# EEM_connector.net
KiCad netlist of a schematic drawn in Altium Designer
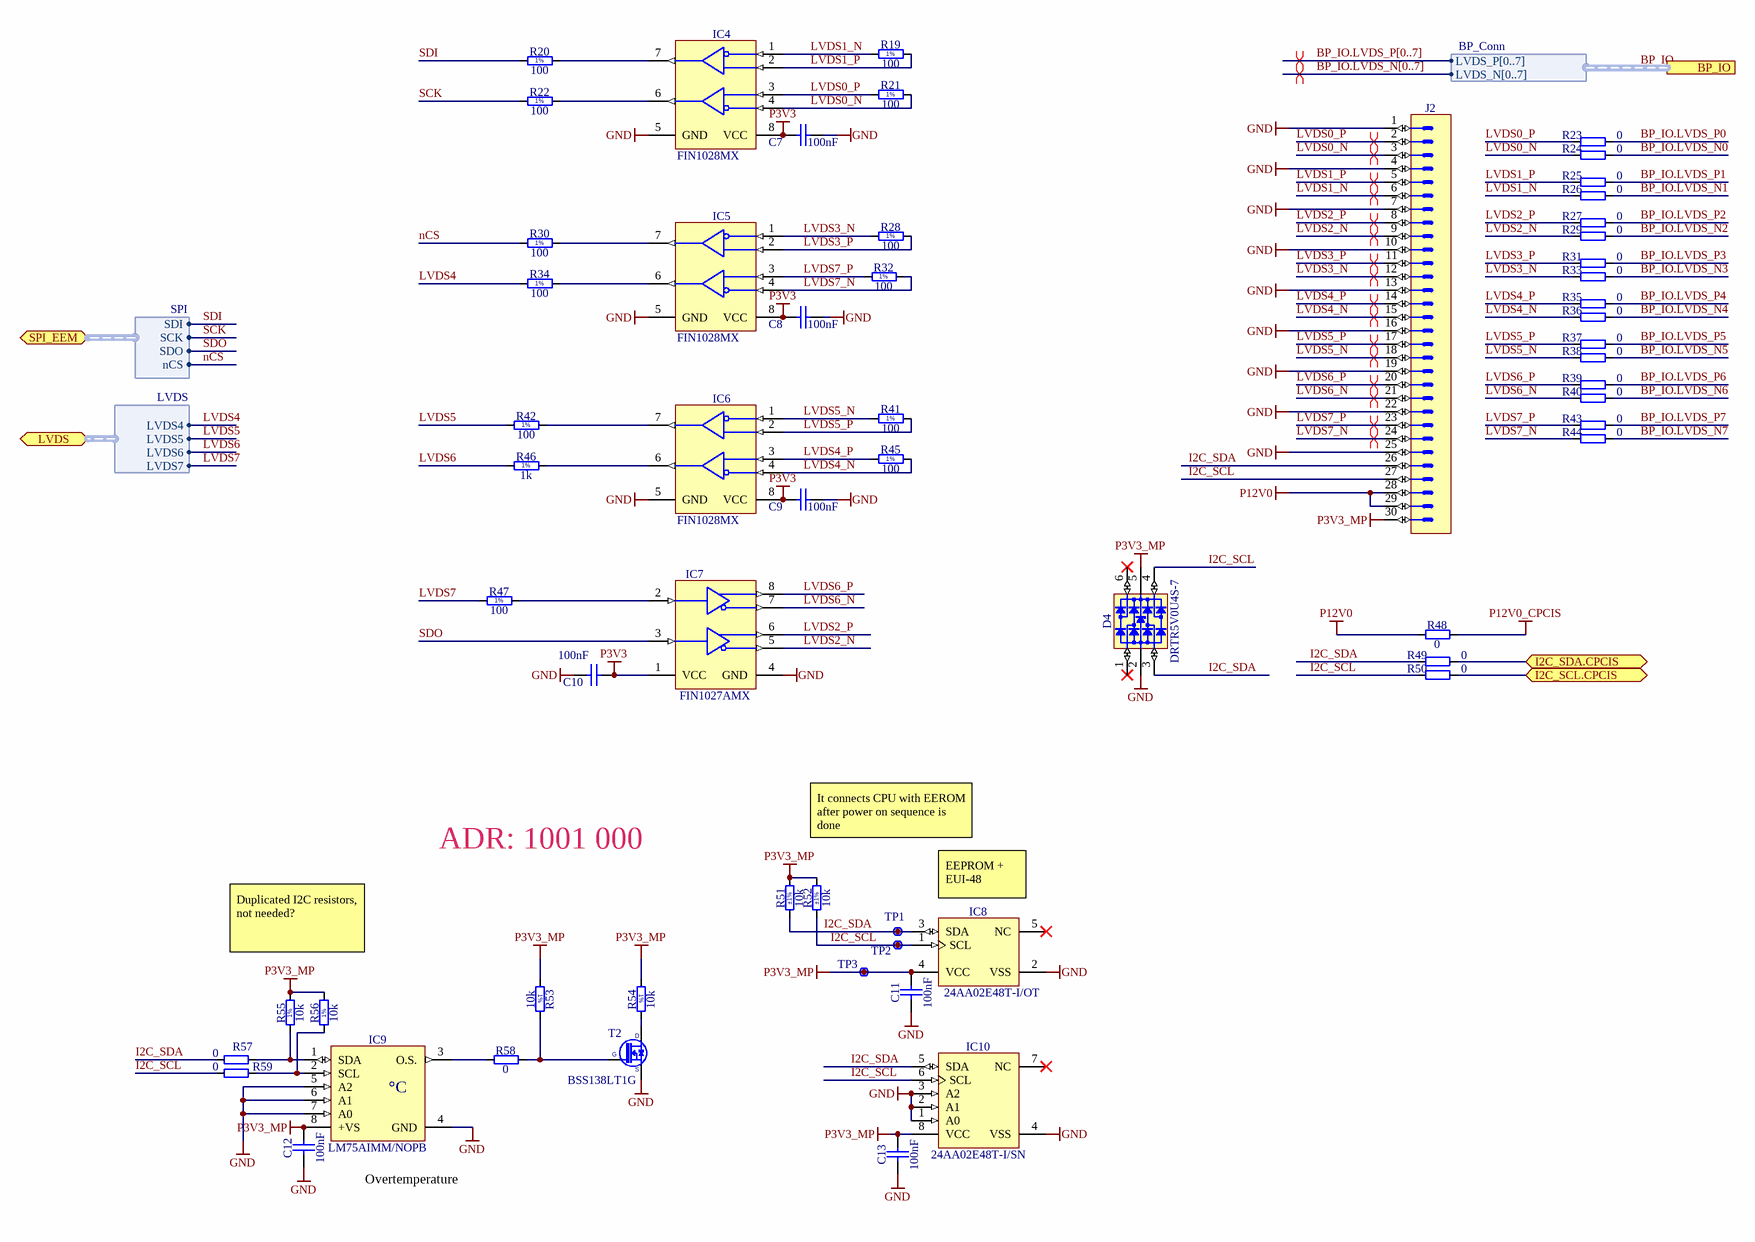
[diagram p0: EEM_connector.SchDoc]

(export (version "E")
  (design (tool "Eeschema 10.0.6"))
  (components
    (comp (ref "C7")
      (value "100nF")
      (footprint "CAPC1005X55N")
      (description "Non-polarised capacitor")
      (fields
        (field (name "PART NUMBER") "CC0402_100NF_16V_10%_X5R")
        (field (name "VOLTAGE") "16V")
        (field (name "AUTHOR") "CERN DEM JLC")
      )
      (libsource (lib "Capacitors") (part "Capacitor - non polarized"))
    )
    (comp (ref "C8")
      (value "100nF")
      (footprint "CAPC1005X55N")
      (description "Non-polarised capacitor")
      (fields
        (field (name "PART NUMBER") "CC0402_100NF_16V_10%_X5R")
        (field (name "VOLTAGE") "16V")
        (field (name "AUTHOR") "CERN DEM JLC")
      )
      (libsource (lib "Capacitors") (part "Capacitor - non polarized"))
    )
    (comp (ref "C9")
      (value "100nF")
      (footprint "CAPC1005X55N")
      (description "Non-polarised capacitor")
      (fields
        (field (name "PART NUMBER") "CC0402_100NF_16V_10%_X5R")
        (field (name "VOLTAGE") "16V")
        (field (name "AUTHOR") "CERN DEM JLC")
      )
      (libsource (lib "Capacitors") (part "Capacitor - non polarized"))
    )
    (comp (ref "C10")
      (value "100nF")
      (footprint "CAPC1005X55N")
      (description "Non-polarised capacitor")
      (fields
        (field (name "PART NUMBER") "CC0402_100NF_16V_10%_X5R")
        (field (name "VOLTAGE") "16V")
        (field (name "AUTHOR") "CERN DEM JLC")
      )
      (libsource (lib "Capacitors") (part "Capacitor - non polarized"))
    )
    (comp (ref "C11")
      (value "100nF")
      (footprint "CAPC1005X55N")
      (description "Non-polarised capacitor")
      (fields
        (field (name "PART NUMBER") "CC0402_100NF_16V_10%_X5R")
        (field (name "VOLTAGE") "16V")
        (field (name "AUTHOR") "CERN DEM JLC")
      )
      (libsource (lib "Capacitors") (part "Capacitor - non polarized"))
    )
    (comp (ref "C12")
      (value "100nF")
      (footprint "CAPC1005X55N")
      (description "Non-polarised capacitor")
      (fields
        (field (name "PART NUMBER") "CC0402_100NF_16V_10%_X5R")
        (field (name "VOLTAGE") "16V")
        (field (name "AUTHOR") "CERN DEM JLC")
      )
      (libsource (lib "Capacitors") (part "Capacitor - non polarized"))
    )
    (comp (ref "C13")
      (value "100nF")
      (footprint "CAPC1005X55N")
      (description "Non-polarised capacitor")
      (fields
        (field (name "PART NUMBER") "CC0402_100NF_16V_10%_X5R")
        (field (name "VOLTAGE") "16V")
        (field (name "AUTHOR") "CERN DEM JLC")
      )
      (libsource (lib "Capacitors") (part "Capacitor - non polarized"))
    )
    (comp (ref "D4")
      (value "DRTR5V0U4S-7")
      (footprint "SOT65P210X110-6N")
      (description "Integrated Quad Ultra-Low Capacitance ESD Protection")
      (fields (field (name "MANUFACTURER") "DIODES") (field (name "AUTHOR") "GK"))
      (libsource (lib "Diodes") (part "D_TVS_DRTR5V0U4S-7"))
    )
    (comp (ref "IC4")
      (value "FIN1028MX")
      (footprint "SOIC127P600X175-8N")
      (description "3.3V LVDS 2-Bit High-Speed Differential Reciever")
      (fields (field (name "MANUFACTURER") "ON Semiconductor") (field (name "AUTHOR") "GK"))
      (libsource (lib "LIBRARY_SCH") (part "IFC_FIN1028"))
    )
    (comp (ref "IC5")
      (value "FIN1028MX")
      (footprint "SOIC127P600X175-8N")
      (description "3.3V LVDS 2-Bit High-Speed Differential Reciever")
      (fields (field (name "MANUFACTURER") "ON Semiconductor") (field (name "AUTHOR") "GK"))
      (libsource (lib "LIBRARY_SCH") (part "IFC_FIN1028"))
    )
    (comp (ref "IC6")
      (value "FIN1028MX")
      (footprint "SOIC127P600X175-8N")
      (description "3.3V LVDS 2-Bit High-Speed Differential Reciever")
      (fields (field (name "MANUFACTURER") "ON Semiconductor") (field (name "AUTHOR") "GK"))
      (libsource (lib "LIBRARY_SCH") (part "IFC_FIN1028"))
    )
    (comp (ref "IC7")
      (value "FIN1027AMX")
      (footprint "SOIC127P600X175-8N")
      (description "3.3V LVDS, 2-Bit, High-Speed, Differential Driver")
      (fields (field (name "MANUFACTURER") "ON Semiconductor") (field (name "AUTHOR") "GK"))
      (libsource (lib "LIBRARY_SCH") (part "IFC_FIN1027A"))
    )
    (comp (ref "IC8")
      (value "24AA02E48T-I/OT")
      (footprint "SOT95P280X145-5N")
      (description "1.7V-5.5V, 2K I2C Serial EEPROM With EUI-48 Node Identity")
      (fields (field (name "MANUFACTURER") "MICROCHIP TECHNOLOGY") (field (name "AUTHOR") "CERN DEM MR"))
      (libsource (lib "ICs And Semiconductors") (part "24AA02E48T-I/OT"))
    )
    (comp (ref "IC9")
      (value "LM75AIMM/NOPB")
      (footprint "SOP65P490X109-8N")
      (description "Digital Temperature Sensor and Thermal Watchdog with Two-Wire Interface")
      (fields (field (name "MANUFACTURER") "TEXAS INSTRUMENTS") (field (name "AUTHOR") "CERN DEM JLC"))
      (libsource (lib "ICs And Semiconductors") (part "LM75"))
    )
    (comp (ref "IC10")
      (value "24AA02E48T-I/SN")
      (footprint "SOIC127P600X175-8N")
      (description "1.7V-5.5V, 2K I2C™ Serial EEPROMs with EUI-48™ Node Identity")
      (fields (field (name "MANUFACTURER") "MICROCHIP TECHNOLOGY") (field (name "AUTHOR") "CERN DEM MR"))
      (libsource (lib "ICs And Semiconductors") (part "24AA025E48-I/SN"))
    )
    (comp (ref "J2")
      (value "IDC")
      (footprint "3M_N2530-6002RB")
      (description "Connector 30 Male")
      (fields
        (field (name "PART NUMBER") "3M_N2530-6002RB")
        (field (name "MANUFACTURER") "3M")
        (field (name "AUTHOR") "CERN DEM JLC")
      )
      (libsource (lib "Connectors") (part "Connector 30 Male"))
    )
    (comp (ref "R19")
      (value "100")
      (footprint "RESC1005X40N")
      (description "Resistor - 1%")
      (fields
        (field (name "PART NUMBER") "R0402_100R_1%_0.0625W_100PPM")
        (field (name "POWER") "0.0625W")
        (field (name "AUTHOR") "CERN DEM JLC")
      )
      (libsource (lib "Resistors") (part "Resistor - 1%"))
    )
    (comp (ref "R20")
      (value "100")
      (footprint "RESC1005X40N")
      (description "Resistor - 1%")
      (fields
        (field (name "PART NUMBER") "R0402_100R_1%_0.0625W_100PPM")
        (field (name "POWER") "0.0625W")
        (field (name "AUTHOR") "CERN DEM JLC")
      )
      (libsource (lib "Resistors") (part "Resistor - 1%"))
    )
    (comp (ref "R21")
      (value "100")
      (footprint "RESC1005X40N")
      (description "Resistor - 1%")
      (fields
        (field (name "PART NUMBER") "R0402_100R_1%_0.0625W_100PPM")
        (field (name "POWER") "0.0625W")
        (field (name "AUTHOR") "CERN DEM JLC")
      )
      (libsource (lib "Resistors") (part "Resistor - 1%"))
    )
    (comp (ref "R22")
      (value "100")
      (footprint "RESC1005X40N")
      (description "Resistor - 1%")
      (fields
        (field (name "PART NUMBER") "R0402_100R_1%_0.0625W_100PPM")
        (field (name "POWER") "0.0625W")
        (field (name "AUTHOR") "CERN DEM JLC")
      )
      (libsource (lib "Resistors") (part "Resistor - 1%"))
    )
    (comp (ref "R23")
      (value "0")
      (footprint "RESC1005X40N")
      (description "Resistor")
      (fields
        (field (name "PART NUMBER") "R0402_0R_JUMPER")
        (field (name "MANUFACTURER") "GENERIC")
        (field (name "AUTHOR") "CERN DEM JLC")
      )
      (libsource (lib "Resistors") (part "Resistor"))
    )
    (comp (ref "R24")
      (value "0")
      (footprint "RESC1005X40N")
      (description "Resistor")
      (fields
        (field (name "PART NUMBER") "R0402_0R_JUMPER")
        (field (name "MANUFACTURER") "GENERIC")
        (field (name "AUTHOR") "CERN DEM JLC")
      )
      (libsource (lib "Resistors") (part "Resistor"))
    )
    (comp (ref "R25")
      (value "0")
      (footprint "RESC1005X40N")
      (description "Resistor")
      (fields
        (field (name "PART NUMBER") "R0402_0R_JUMPER")
        (field (name "MANUFACTURER") "GENERIC")
        (field (name "AUTHOR") "CERN DEM JLC")
      )
      (libsource (lib "Resistors") (part "Resistor"))
    )
    (comp (ref "R26")
      (value "0")
      (footprint "RESC1005X40N")
      (description "Resistor")
      (fields
        (field (name "PART NUMBER") "R0402_0R_JUMPER")
        (field (name "MANUFACTURER") "GENERIC")
        (field (name "AUTHOR") "CERN DEM JLC")
      )
      (libsource (lib "Resistors") (part "Resistor"))
    )
    (comp (ref "R27")
      (value "0")
      (footprint "RESC1005X40N")
      (description "Resistor")
      (fields
        (field (name "PART NUMBER") "R0402_0R_JUMPER")
        (field (name "MANUFACTURER") "GENERIC")
        (field (name "AUTHOR") "CERN DEM JLC")
      )
      (libsource (lib "Resistors") (part "Resistor"))
    )
    (comp (ref "R28")
      (value "100")
      (footprint "RESC1005X40N")
      (description "Resistor - 1%")
      (fields
        (field (name "PART NUMBER") "R0402_100R_1%_0.0625W_100PPM")
        (field (name "POWER") "0.0625W")
        (field (name "AUTHOR") "CERN DEM JLC")
      )
      (libsource (lib "Resistors") (part "Resistor - 1%"))
    )
    (comp (ref "R29")
      (value "0")
      (footprint "RESC1005X40N")
      (description "Resistor")
      (fields
        (field (name "PART NUMBER") "R0402_0R_JUMPER")
        (field (name "MANUFACTURER") "GENERIC")
        (field (name "AUTHOR") "CERN DEM JLC")
      )
      (libsource (lib "Resistors") (part "Resistor"))
    )
    (comp (ref "R30")
      (value "100")
      (footprint "RESC1005X40N")
      (description "Resistor - 1%")
      (fields
        (field (name "PART NUMBER") "R0402_100R_1%_0.0625W_100PPM")
        (field (name "POWER") "0.0625W")
        (field (name "AUTHOR") "CERN DEM JLC")
      )
      (libsource (lib "Resistors") (part "Resistor - 1%"))
    )
    (comp (ref "R31")
      (value "0")
      (footprint "RESC1005X40N")
      (description "Resistor")
      (fields
        (field (name "PART NUMBER") "R0402_0R_JUMPER")
        (field (name "MANUFACTURER") "GENERIC")
        (field (name "AUTHOR") "CERN DEM JLC")
      )
      (libsource (lib "Resistors") (part "Resistor"))
    )
    (comp (ref "R32")
      (value "100")
      (footprint "RESC1005X40N")
      (description "Resistor - 1%")
      (fields
        (field (name "PART NUMBER") "R0402_100R_1%_0.0625W_100PPM")
        (field (name "POWER") "0.0625W")
        (field (name "AUTHOR") "CERN DEM JLC")
      )
      (libsource (lib "Resistors") (part "Resistor - 1%"))
    )
    (comp (ref "R33")
      (value "0")
      (footprint "RESC1005X40N")
      (description "Resistor")
      (fields
        (field (name "PART NUMBER") "R0402_0R_JUMPER")
        (field (name "MANUFACTURER") "GENERIC")
        (field (name "AUTHOR") "CERN DEM JLC")
      )
      (libsource (lib "Resistors") (part "Resistor"))
    )
    (comp (ref "R34")
      (value "100")
      (footprint "RESC1005X40N")
      (description "Resistor - 1%")
      (fields
        (field (name "PART NUMBER") "R0402_100R_1%_0.0625W_100PPM")
        (field (name "POWER") "0.0625W")
        (field (name "AUTHOR") "CERN DEM JLC")
      )
      (libsource (lib "Resistors") (part "Resistor - 1%"))
    )
    (comp (ref "R35")
      (value "0")
      (footprint "RESC1005X40N")
      (description "Resistor")
      (fields
        (field (name "PART NUMBER") "R0402_0R_JUMPER")
        (field (name "MANUFACTURER") "GENERIC")
        (field (name "AUTHOR") "CERN DEM JLC")
      )
      (libsource (lib "Resistors") (part "Resistor"))
    )
    (comp (ref "R36")
      (value "0")
      (footprint "RESC1005X40N")
      (description "Resistor")
      (fields
        (field (name "PART NUMBER") "R0402_0R_JUMPER")
        (field (name "MANUFACTURER") "GENERIC")
        (field (name "AUTHOR") "CERN DEM JLC")
      )
      (libsource (lib "Resistors") (part "Resistor"))
    )
    (comp (ref "R37")
      (value "0")
      (footprint "RESC1005X40N")
      (description "Resistor")
      (fields
        (field (name "PART NUMBER") "R0402_0R_JUMPER")
        (field (name "MANUFACTURER") "GENERIC")
        (field (name "AUTHOR") "CERN DEM JLC")
      )
      (libsource (lib "Resistors") (part "Resistor"))
    )
    (comp (ref "R38")
      (value "0")
      (footprint "RESC1005X40N")
      (description "Resistor")
      (fields
        (field (name "PART NUMBER") "R0402_0R_JUMPER")
        (field (name "MANUFACTURER") "GENERIC")
        (field (name "AUTHOR") "CERN DEM JLC")
      )
      (libsource (lib "Resistors") (part "Resistor"))
    )
    (comp (ref "R39")
      (value "0")
      (footprint "RESC1005X40N")
      (description "Resistor")
      (fields
        (field (name "PART NUMBER") "R0402_0R_JUMPER")
        (field (name "MANUFACTURER") "GENERIC")
        (field (name "AUTHOR") "CERN DEM JLC")
      )
      (libsource (lib "Resistors") (part "Resistor"))
    )
    (comp (ref "R40")
      (value "0")
      (footprint "RESC1005X40N")
      (description "Resistor")
      (fields
        (field (name "PART NUMBER") "R0402_0R_JUMPER")
        (field (name "MANUFACTURER") "GENERIC")
        (field (name "AUTHOR") "CERN DEM JLC")
      )
      (libsource (lib "Resistors") (part "Resistor"))
    )
    (comp (ref "R41")
      (value "100")
      (footprint "RESC1005X40N")
      (description "Resistor - 1%")
      (fields
        (field (name "PART NUMBER") "R0402_100R_1%_0.0625W_100PPM")
        (field (name "POWER") "0.0625W")
        (field (name "AUTHOR") "CERN DEM JLC")
      )
      (libsource (lib "Resistors") (part "Resistor - 1%"))
    )
    (comp (ref "R42")
      (value "100")
      (footprint "RESC1005X40N")
      (description "Resistor - 1%")
      (fields
        (field (name "PART NUMBER") "R0402_100R_1%_0.0625W_100PPM")
        (field (name "POWER") "0.0625W")
        (field (name "AUTHOR") "CERN DEM JLC")
      )
      (libsource (lib "Resistors") (part "Resistor - 1%"))
    )
    (comp (ref "R43")
      (value "0")
      (footprint "RESC1005X40N")
      (description "Resistor")
      (fields
        (field (name "PART NUMBER") "R0402_0R_JUMPER")
        (field (name "MANUFACTURER") "GENERIC")
        (field (name "AUTHOR") "CERN DEM JLC")
      )
      (libsource (lib "Resistors") (part "Resistor"))
    )
    (comp (ref "R44")
      (value "0")
      (footprint "RESC1005X40N")
      (description "Resistor")
      (fields
        (field (name "PART NUMBER") "R0402_0R_JUMPER")
        (field (name "MANUFACTURER") "GENERIC")
        (field (name "AUTHOR") "CERN DEM JLC")
      )
      (libsource (lib "Resistors") (part "Resistor"))
    )
    (comp (ref "R45")
      (value "100")
      (footprint "RESC1005X40N")
      (description "Resistor - 1%")
      (fields
        (field (name "PART NUMBER") "R0402_100R_1%_0.0625W_100PPM")
        (field (name "POWER") "0.0625W")
        (field (name "AUTHOR") "CERN DEM JLC")
      )
      (libsource (lib "Resistors") (part "Resistor - 1%"))
    )
    (comp (ref "R46")
      (value "1k")
      (footprint "RESC1005X40N")
      (description "Resistor - 1%")
      (fields
        (field (name "PART NUMBER") "R0402_1K_1%_0.0625W_100PPM")
        (field (name "POWER") "0.0625W")
        (field (name "AUTHOR") "CERN DEM JLC")
      )
      (libsource (lib "Resistors") (part "Resistor - 1%"))
    )
    (comp (ref "R47")
      (value "100")
      (footprint "RESC1005X40N")
      (description "Resistor - 1%")
      (fields
        (field (name "PART NUMBER") "R0402_100R_1%_0.0625W_100PPM")
        (field (name "POWER") "0.0625W")
        (field (name "AUTHOR") "CERN DEM JLC")
      )
      (libsource (lib "Resistors") (part "Resistor - 1%"))
    )
    (comp (ref "R48")
      (value "0")
      (footprint "RESC2012X60N")
      (description "Resistor")
      (fields
        (field (name "PART NUMBER") "R0805_0R_JUMPER")
        (field (name "MANUFACTURER") "GENERIC")
        (field (name "AUTHOR") "CERN DEM JLC")
      )
      (libsource (lib "Resistors") (part "Resistor"))
    )
    (comp (ref "R49")
      (value "0")
      (footprint "RESC1005X40N")
      (description "Resistor")
      (fields
        (field (name "PART NUMBER") "R0402_0R_JUMPER")
        (field (name "MANUFACTURER") "GENERIC")
        (field (name "AUTHOR") "CERN DEM JLC")
      )
      (libsource (lib "Resistors") (part "Resistor"))
    )
    (comp (ref "R50")
      (value "0")
      (footprint "RESC1005X40N")
      (description "Resistor")
      (fields
        (field (name "PART NUMBER") "R0402_0R_JUMPER")
        (field (name "MANUFACTURER") "GENERIC")
        (field (name "AUTHOR") "CERN DEM JLC")
      )
      (libsource (lib "Resistors") (part "Resistor"))
    )
    (comp (ref "R51")
      (value "10k")
      (footprint "RESC1005X40N")
      (description "Resistor - 1%")
      (fields
        (field (name "TOLERANCE") "±1%")
        (field (name "PART NUMBER") "R0402_10K_1%_0.0625W_100PPM")
        (field (name "POWER") "0.0625W")
        (field (name "AUTHOR") "CERN DEM JLC")
      )
      (libsource (lib "Resistors") (part "Resistor - 1%"))
    )
    (comp (ref "R52")
      (value "10k")
      (footprint "RESC1005X40N")
      (description "Resistor - 1%")
      (fields
        (field (name "TOLERANCE") "±1%")
        (field (name "PART NUMBER") "R0402_10K_1%_0.0625W_100PPM")
        (field (name "POWER") "0.0625W")
        (field (name "AUTHOR") "CERN DEM JLC")
      )
      (libsource (lib "Resistors") (part "Resistor - 1%"))
    )
    (comp (ref "R53")
      (value "10k")
      (footprint "RESC1005X40N")
      (description "Resistor - 1%")
      (fields
        (field (name "PART NUMBER") "R0402_10K_1%_0.0625W_100PPM")
        (field (name "POWER") "0.0625W")
        (field (name "AUTHOR") "CERN DEM JLC")
      )
      (libsource (lib "Resistors") (part "Resistor - 1%"))
    )
    (comp (ref "R54")
      (value "10k")
      (footprint "RESC1005X40N")
      (description "Resistor - 1%")
      (fields
        (field (name "PART NUMBER") "R0402_10K_1%_0.0625W_100PPM")
        (field (name "POWER") "0.0625W")
        (field (name "AUTHOR") "CERN DEM JLC")
      )
      (libsource (lib "Resistors") (part "Resistor - 1%"))
    )
    (comp (ref "R55")
      (value "10k")
      (footprint "RESC1005X40N")
      (description "Resistor - 1%")
      (fields
        (field (name "PART NUMBER") "R0402_10K_1%_0.0625W_100PPM")
        (field (name "POWER") "0.0625W")
        (field (name "AUTHOR") "CERN DEM JLC")
      )
      (libsource (lib "Resistors") (part "Resistor - 1%"))
    )
    (comp (ref "R56")
      (value "10k")
      (footprint "RESC1005X40N")
      (description "Resistor - 1%")
      (fields
        (field (name "PART NUMBER") "R0402_10K_1%_0.0625W_100PPM")
        (field (name "POWER") "0.0625W")
        (field (name "AUTHOR") "CERN DEM JLC")
      )
      (libsource (lib "Resistors") (part "Resistor - 1%"))
    )
    (comp (ref "R57")
      (value "0")
      (footprint "RESC1005X40N")
      (description "Resistor")
      (fields
        (field (name "PART NUMBER") "R0402_0R_JUMPER")
        (field (name "MANUFACTURER") "GENERIC")
        (field (name "AUTHOR") "CERN DEM JLC")
      )
      (libsource (lib "Resistors") (part "Resistor"))
    )
    (comp (ref "R58")
      (value "0")
      (footprint "RESC1005X40N")
      (description "Resistor")
      (fields
        (field (name "PART NUMBER") "R0402_0R_JUMPER")
        (field (name "MANUFACTURER") "GENERIC")
        (field (name "AUTHOR") "CERN DEM JLC")
      )
      (libsource (lib "Resistors") (part "Resistor"))
    )
    (comp (ref "R59")
      (value "0")
      (footprint "RESC1005X40N")
      (description "Resistor")
      (fields
        (field (name "PART NUMBER") "R0402_0R_JUMPER")
        (field (name "MANUFACTURER") "GENERIC")
        (field (name "AUTHOR") "CERN DEM JLC")
      )
      (libsource (lib "Resistors") (part "Resistor"))
    )
    (comp (ref "T2")
      (value "BSS138LT1G")
      (footprint "SOT95P240X110-3N")
      (description "N-CHANNEL MOSFET WITH DIODE")
      (fields (field (name "MANUFACTURER") "ON SEMICONDUCTOR") (field (name "AUTHOR") "CERN DEM JLC"))
      (libsource (lib "ICs And Semiconductors") (part "N-MOSFET-D 1G 2S 3D"))
    )
    (comp (ref "TP1")
      (value "Test Point")
      (footprint "TPS127")
      (fields (field (name "PART NUMBER") "SMD_PAD_1.27X1.27MM") (field (name "AUTHOR") "CERN DEM JLC"))
      (libsource (lib "Eletro-mechanical") (part "Test Point"))
    )
    (comp (ref "TP2")
      (value "Test Point")
      (footprint "TPS127")
      (fields (field (name "PART NUMBER") "SMD_PAD_1.27X1.27MM") (field (name "AUTHOR") "CERN DEM JLC"))
      (libsource (lib "Eletro-mechanical") (part "Test Point"))
    )
    (comp (ref "TP3")
      (value "Test Point")
      (footprint "TPS127")
      (fields (field (name "PART NUMBER") "SMD_PAD_1.27X1.27MM") (field (name "AUTHOR") "CERN DEM JLC"))
      (libsource (lib "Eletro-mechanical") (part "Test Point"))
    )
  )
  (nets
    (net (code "4") (name "/BP_IO.LVDS_N0") (class "Default")
      (node (ref "R24") (pin "2") (pinfunction "2_2") (pintype "passive"))
    )
    (net (code "5") (name "/BP_IO.LVDS_N1") (class "Default")
      (node (ref "R26") (pin "2") (pinfunction "2_2") (pintype "passive"))
    )
    (net (code "6") (name "/BP_IO.LVDS_N2") (class "Default")
      (node (ref "R29") (pin "2") (pinfunction "2_2") (pintype "passive"))
    )
    (net (code "7") (name "/BP_IO.LVDS_N3") (class "Default")
      (node (ref "R33") (pin "2") (pinfunction "2_2") (pintype "passive"))
    )
    (net (code "8") (name "/BP_IO.LVDS_N4") (class "Default")
      (node (ref "R36") (pin "2") (pinfunction "2_2") (pintype "passive"))
    )
    (net (code "9") (name "/BP_IO.LVDS_N5") (class "Default")
      (node (ref "R38") (pin "2") (pinfunction "2_2") (pintype "passive"))
    )
    (net (code "10") (name "/BP_IO.LVDS_N6") (class "Default")
      (node (ref "R40") (pin "2") (pinfunction "2_2") (pintype "passive"))
    )
    (net (code "11") (name "/BP_IO.LVDS_N7") (class "Default")
      (node (ref "R44") (pin "2") (pinfunction "2_2") (pintype "passive"))
    )
    (net (code "13") (name "/BP_IO.LVDS_P0") (class "Default")
      (node (ref "R23") (pin "2") (pinfunction "2_2") (pintype "passive"))
    )
    (net (code "14") (name "/BP_IO.LVDS_P1") (class "Default")
      (node (ref "R25") (pin "2") (pinfunction "2_2") (pintype "passive"))
    )
    (net (code "15") (name "/BP_IO.LVDS_P2") (class "Default")
      (node (ref "R27") (pin "2") (pinfunction "2_2") (pintype "passive"))
    )
    (net (code "16") (name "/BP_IO.LVDS_P3") (class "Default")
      (node (ref "R31") (pin "2") (pinfunction "2_2") (pintype "passive"))
    )
    (net (code "17") (name "/BP_IO.LVDS_P4") (class "Default")
      (node (ref "R35") (pin "2") (pinfunction "2_2") (pintype "passive"))
    )
    (net (code "18") (name "/BP_IO.LVDS_P5") (class "Default")
      (node (ref "R37") (pin "2") (pinfunction "2_2") (pintype "passive"))
    )
    (net (code "19") (name "/BP_IO.LVDS_P6") (class "Default")
      (node (ref "R39") (pin "2") (pinfunction "2_2") (pintype "passive"))
    )
    (net (code "20") (name "/BP_IO.LVDS_P7") (class "Default")
      (node (ref "R43") (pin "2") (pinfunction "2_2") (pintype "passive"))
    )
    (net (code "23") (name "/I2C_SCL") (class "Default")
      (node (ref "D4") (pin "4") (pinfunction "I/O3_4") (pintype "bidirectional"))
      (node (ref "IC10") (pin "6") (pinfunction "SCL_6") (pintype "input"))
      (node (ref "IC8") (pin "1") (pinfunction "SCL_1") (pintype "input"))
      (node (ref "J2") (pin "27") (pinfunction "27_27") (pintype "bidirectional"))
      (node (ref "R50") (pin "1") (pinfunction "1_1") (pintype "passive"))
      (node (ref "R52") (pin "1") (pinfunction "1_1") (pintype "passive"))
      (node (ref "R59") (pin "1") (pinfunction "1_1") (pintype "passive"))
      (node (ref "TP2") (pin "1") (pinfunction "1_1") (pintype "bidirectional"))
    )
    (net (code "24") (name "/I2C_SCL.CPCIS") (class "Default")
      (node (ref "R50") (pin "2") (pinfunction "2_2") (pintype "passive"))
    )
    (net (code "25") (name "/I2C_SDA") (class "Default")
      (node (ref "D4") (pin "3") (pinfunction "I/O2_3") (pintype "bidirectional"))
      (node (ref "IC10") (pin "5") (pinfunction "SDA_5") (pintype "bidirectional"))
      (node (ref "IC8") (pin "3") (pinfunction "SDA_3") (pintype "bidirectional"))
      (node (ref "J2") (pin "26") (pinfunction "26_26") (pintype "bidirectional"))
      (node (ref "R49") (pin "1") (pinfunction "1_1") (pintype "passive"))
      (node (ref "R51") (pin "1") (pinfunction "1_1") (pintype "passive"))
      (node (ref "R57") (pin "1") (pinfunction "1_1") (pintype "passive"))
      (node (ref "TP1") (pin "1") (pinfunction "1_1") (pintype "bidirectional"))
    )
    (net (code "26") (name "/I2C_SDA.CPCIS") (class "Default")
      (node (ref "R49") (pin "2") (pinfunction "2_2") (pintype "passive"))
    )
    (net (code "27") (name "/LVDS0_N") (class "Default")
      (node (ref "IC4") (pin "4") (pinfunction "RIN2-_4") (pintype "input"))
      (node (ref "J2") (pin "3") (pinfunction "3_3") (pintype "bidirectional"))
      (node (ref "R21") (pin "2") (pinfunction "2_2") (pintype "passive"))
      (node (ref "R24") (pin "1") (pinfunction "1_1") (pintype "passive"))
    )
    (net (code "28") (name "/LVDS0_P") (class "Default")
      (node (ref "IC4") (pin "3") (pinfunction "RIN2+_3") (pintype "input"))
      (node (ref "J2") (pin "2") (pinfunction "2_2") (pintype "bidirectional"))
      (node (ref "R21") (pin "1") (pinfunction "1_1") (pintype "passive"))
      (node (ref "R23") (pin "1") (pinfunction "1_1") (pintype "passive"))
    )
    (net (code "29") (name "/LVDS1_N") (class "Default")
      (node (ref "IC4") (pin "1") (pinfunction "RIN1-_1") (pintype "input"))
      (node (ref "J2") (pin "6") (pinfunction "6_6") (pintype "bidirectional"))
      (node (ref "R19") (pin "1") (pinfunction "1_1") (pintype "passive"))
      (node (ref "R26") (pin "1") (pinfunction "1_1") (pintype "passive"))
    )
    (net (code "30") (name "/LVDS1_P") (class "Default")
      (node (ref "IC4") (pin "2") (pinfunction "RIN1+_2") (pintype "input"))
      (node (ref "J2") (pin "5") (pinfunction "5_5") (pintype "bidirectional"))
      (node (ref "R19") (pin "2") (pinfunction "2_2") (pintype "passive"))
      (node (ref "R25") (pin "1") (pinfunction "1_1") (pintype "passive"))
    )
    (net (code "31") (name "/LVDS2_N") (class "Default")
      (node (ref "IC7") (pin "5") (pinfunction "DOUT-_5") (pintype "output"))
      (node (ref "J2") (pin "9") (pinfunction "9_9") (pintype "bidirectional"))
      (node (ref "R29") (pin "1") (pinfunction "1_1") (pintype "passive"))
    )
    (net (code "32") (name "/LVDS2_P") (class "Default")
      (node (ref "IC7") (pin "6") (pinfunction "DOUT+_6") (pintype "output"))
      (node (ref "J2") (pin "8") (pinfunction "8_8") (pintype "bidirectional"))
      (node (ref "R27") (pin "1") (pinfunction "1_1") (pintype "passive"))
    )
    (net (code "33") (name "/LVDS3_N") (class "Default")
      (node (ref "IC5") (pin "1") (pinfunction "RIN1-_1") (pintype "input"))
      (node (ref "J2") (pin "12") (pinfunction "12_12") (pintype "bidirectional"))
      (node (ref "R28") (pin "1") (pinfunction "1_1") (pintype "passive"))
      (node (ref "R33") (pin "1") (pinfunction "1_1") (pintype "passive"))
    )
    (net (code "34") (name "/LVDS3_P") (class "Default")
      (node (ref "IC5") (pin "2") (pinfunction "RIN1+_2") (pintype "input"))
      (node (ref "J2") (pin "11") (pinfunction "11_11") (pintype "bidirectional"))
      (node (ref "R28") (pin "2") (pinfunction "2_2") (pintype "passive"))
      (node (ref "R31") (pin "1") (pinfunction "1_1") (pintype "passive"))
    )
    (net (code "35") (name "/LVDS4") (class "Default")
      (node (ref "R34") (pin "1") (pinfunction "1_1") (pintype "passive"))
    )
    (net (code "36") (name "/LVDS4_N") (class "Default")
      (node (ref "IC6") (pin "4") (pinfunction "RIN2-_4") (pintype "input"))
      (node (ref "J2") (pin "15") (pinfunction "15_15") (pintype "bidirectional"))
      (node (ref "R36") (pin "1") (pinfunction "1_1") (pintype "passive"))
      (node (ref "R45") (pin "2") (pinfunction "2_2") (pintype "passive"))
    )
    (net (code "37") (name "/LVDS4_P") (class "Default")
      (node (ref "IC6") (pin "3") (pinfunction "RIN2+_3") (pintype "input"))
      (node (ref "J2") (pin "14") (pinfunction "14_14") (pintype "bidirectional"))
      (node (ref "R35") (pin "1") (pinfunction "1_1") (pintype "passive"))
      (node (ref "R45") (pin "1") (pinfunction "1_1") (pintype "passive"))
    )
    (net (code "38") (name "/LVDS5") (class "Default")
      (node (ref "R42") (pin "1") (pinfunction "1_1") (pintype "passive"))
    )
    (net (code "39") (name "/LVDS5_N") (class "Default")
      (node (ref "IC6") (pin "1") (pinfunction "RIN1-_1") (pintype "input"))
      (node (ref "J2") (pin "18") (pinfunction "18_18") (pintype "bidirectional"))
      (node (ref "R38") (pin "1") (pinfunction "1_1") (pintype "passive"))
      (node (ref "R41") (pin "1") (pinfunction "1_1") (pintype "passive"))
    )
    (net (code "40") (name "/LVDS5_P") (class "Default")
      (node (ref "IC6") (pin "2") (pinfunction "RIN1+_2") (pintype "input"))
      (node (ref "J2") (pin "17") (pinfunction "17_17") (pintype "bidirectional"))
      (node (ref "R37") (pin "1") (pinfunction "1_1") (pintype "passive"))
      (node (ref "R41") (pin "2") (pinfunction "2_2") (pintype "passive"))
    )
    (net (code "41") (name "/LVDS6") (class "Default")
      (node (ref "R46") (pin "1") (pinfunction "1_1") (pintype "passive"))
    )
    (net (code "42") (name "/LVDS6_N") (class "Default")
      (node (ref "IC7") (pin "7") (pinfunction "DOUT-_7") (pintype "output"))
      (node (ref "J2") (pin "21") (pinfunction "21_21") (pintype "bidirectional"))
      (node (ref "R40") (pin "1") (pinfunction "1_1") (pintype "passive"))
    )
    (net (code "43") (name "/LVDS6_P") (class "Default")
      (node (ref "IC7") (pin "8") (pinfunction "DOUT+_8") (pintype "output"))
      (node (ref "J2") (pin "20") (pinfunction "20_20") (pintype "bidirectional"))
      (node (ref "R39") (pin "1") (pinfunction "1_1") (pintype "passive"))
    )
    (net (code "44") (name "/LVDS7") (class "Default")
      (node (ref "R47") (pin "1") (pinfunction "1_1") (pintype "passive"))
    )
    (net (code "45") (name "/LVDS7_N") (class "Default")
      (node (ref "IC5") (pin "4") (pinfunction "RIN2-_4") (pintype "input"))
      (node (ref "J2") (pin "24") (pinfunction "24_24") (pintype "bidirectional"))
      (node (ref "R32") (pin "2") (pinfunction "2_2") (pintype "passive"))
      (node (ref "R44") (pin "1") (pinfunction "1_1") (pintype "passive"))
    )
    (net (code "46") (name "/LVDS7_P") (class "Default")
      (node (ref "IC5") (pin "3") (pinfunction "RIN2+_3") (pintype "input"))
      (node (ref "J2") (pin "23") (pinfunction "23_23") (pintype "bidirectional"))
      (node (ref "R32") (pin "1") (pinfunction "1_1") (pintype "passive"))
      (node (ref "R43") (pin "1") (pinfunction "1_1") (pintype "passive"))
    )
    (net (code "47") (name "/SCK") (class "Default")
      (node (ref "R22") (pin "1") (pinfunction "1_1") (pintype "passive"))
    )
    (net (code "48") (name "/SDI") (class "Default")
      (node (ref "R20") (pin "1") (pinfunction "1_1") (pintype "passive"))
    )
    (net (code "49") (name "/SDO") (class "Default")
      (node (ref "IC7") (pin "3") (pinfunction "DIN2RIN-_3") (pintype "input"))
    )
    (net (code "50") (name "/nCS") (class "Default")
      (node (ref "R30") (pin "1") (pinfunction "1_1") (pintype "passive"))
    )
    (net (code "53") (name "GND") (class "Default")
      (node (ref "C10") (pin "1") (pinfunction "1_1") (pintype "passive"))
      (node (ref "C11") (pin "1") (pinfunction "1_1") (pintype "passive"))
      (node (ref "C12") (pin "1") (pinfunction "1_1") (pintype "passive"))
      (node (ref "C13") (pin "1") (pinfunction "1_1") (pintype "passive"))
      (node (ref "C7") (pin "1") (pinfunction "1_1") (pintype "passive"))
      (node (ref "C8") (pin "1") (pinfunction "1_1") (pintype "passive"))
      (node (ref "C9") (pin "1") (pinfunction "1_1") (pintype "passive"))
      (node (ref "D4") (pin "2") (pinfunction "GND_2") (pintype "power_in"))
      (node (ref "IC10") (pin "1") (pinfunction "A0_1") (pintype "input"))
      (node (ref "IC10") (pin "2") (pinfunction "A1_2") (pintype "input"))
      (node (ref "IC10") (pin "3") (pinfunction "A2_3") (pintype "input"))
      (node (ref "IC10") (pin "4") (pinfunction "VSS_4") (pintype "power_in"))
      (node (ref "IC4") (pin "5") (pinfunction "GND_5") (pintype "power_in"))
      (node (ref "IC5") (pin "5") (pinfunction "GND_5") (pintype "power_in"))
      (node (ref "IC6") (pin "5") (pinfunction "GND_5") (pintype "power_in"))
      (node (ref "IC7") (pin "4") (pinfunction "GND_4") (pintype "power_in"))
      (node (ref "IC8") (pin "2") (pinfunction "VSS_2") (pintype "power_in"))
      (node (ref "IC9") (pin "4") (pinfunction "GND_4") (pintype "power_in"))
      (node (ref "IC9") (pin "5") (pinfunction "A2_5") (pintype "input"))
      (node (ref "IC9") (pin "6") (pinfunction "A1_6") (pintype "input"))
      (node (ref "IC9") (pin "7") (pinfunction "A0_7") (pintype "input"))
      (node (ref "J2") (pin "1") (pinfunction "1_1") (pintype "bidirectional"))
      (node (ref "J2") (pin "10") (pinfunction "10_10") (pintype "bidirectional"))
      (node (ref "J2") (pin "13") (pinfunction "13_13") (pintype "bidirectional"))
      (node (ref "J2") (pin "16") (pinfunction "16_16") (pintype "bidirectional"))
      (node (ref "J2") (pin "19") (pinfunction "19_19") (pintype "bidirectional"))
      (node (ref "J2") (pin "22") (pinfunction "22_22") (pintype "bidirectional"))
      (node (ref "J2") (pin "25") (pinfunction "25_25") (pintype "bidirectional"))
      (node (ref "J2") (pin "4") (pinfunction "4_4") (pintype "bidirectional"))
      (node (ref "J2") (pin "7") (pinfunction "7_7") (pintype "bidirectional"))
      (node (ref "T2") (pin "2") (pinfunction "S_2") (pintype "passive"))
    )
    (net (code "54") (name "Net-(IC4-ROUT1)") (class "Default")
      (node (ref "IC4") (pin "7") (pinfunction "ROUT1_7") (pintype "output"))
      (node (ref "R20") (pin "2") (pinfunction "2_2") (pintype "passive"))
    )
    (net (code "55") (name "Net-(IC4-ROUT2)") (class "Default")
      (node (ref "IC4") (pin "6") (pinfunction "ROUT2_6") (pintype "output"))
      (node (ref "R22") (pin "2") (pinfunction "2_2") (pintype "passive"))
    )
    (net (code "56") (name "Net-(IC5-ROUT1)") (class "Default")
      (node (ref "IC5") (pin "7") (pinfunction "ROUT1_7") (pintype "output"))
      (node (ref "R30") (pin "2") (pinfunction "2_2") (pintype "passive"))
    )
    (net (code "57") (name "Net-(IC5-ROUT2)") (class "Default")
      (node (ref "IC5") (pin "6") (pinfunction "ROUT2_6") (pintype "output"))
      (node (ref "R34") (pin "2") (pinfunction "2_2") (pintype "passive"))
    )
    (net (code "58") (name "Net-(IC6-ROUT1)") (class "Default")
      (node (ref "IC6") (pin "7") (pinfunction "ROUT1_7") (pintype "output"))
      (node (ref "R42") (pin "2") (pinfunction "2_2") (pintype "passive"))
    )
    (net (code "59") (name "Net-(IC6-ROUT2)") (class "Default")
      (node (ref "IC6") (pin "6") (pinfunction "ROUT2_6") (pintype "output"))
      (node (ref "R46") (pin "2") (pinfunction "2_2") (pintype "passive"))
    )
    (net (code "60") (name "Net-(IC7-DIN1)") (class "Default")
      (node (ref "IC7") (pin "2") (pinfunction "DIN1_2") (pintype "input"))
      (node (ref "R47") (pin "2") (pinfunction "2_2") (pintype "passive"))
    )
    (net (code "61") (name "Net-(IC9-O.S.)") (class "Default")
      (node (ref "IC9") (pin "3") (pinfunction "O.S._3") (pintype "output"))
      (node (ref "R58") (pin "1") (pinfunction "1_1") (pintype "passive"))
    )
    (net (code "62") (name "Net-(IC9-SCL)") (class "Default")
      (node (ref "IC9") (pin "2") (pinfunction "SCL_2") (pintype "input"))
      (node (ref "R56") (pin "1") (pinfunction "1_1") (pintype "passive"))
      (node (ref "R59") (pin "2") (pinfunction "2_2") (pintype "passive"))
    )
    (net (code "63") (name "Net-(IC9-SDA)") (class "Default")
      (node (ref "IC9") (pin "1") (pinfunction "SDA_1") (pintype "bidirectional"))
      (node (ref "R55") (pin "1") (pinfunction "1_1") (pintype "passive"))
      (node (ref "R57") (pin "2") (pinfunction "2_2") (pintype "passive"))
    )
    (net (code "64") (name "Net-(T2-D)") (class "Default")
      (node (ref "R54") (pin "2") (pinfunction "2_2") (pintype "passive"))
      (node (ref "T2") (pin "3") (pinfunction "D_3") (pintype "passive"))
    )
    (net (code "65") (name "Net-(T2-G)") (class "Default")
      (node (ref "R53") (pin "2") (pinfunction "2_2") (pintype "passive"))
      (node (ref "R58") (pin "2") (pinfunction "2_2") (pintype "passive"))
      (node (ref "T2") (pin "1") (pinfunction "G_1") (pintype "passive"))
    )
    (net (code "66") (name "P3V3") (class "Default")
      (node (ref "C10") (pin "2") (pinfunction "2_2") (pintype "passive"))
      (node (ref "C7") (pin "2") (pinfunction "2_2") (pintype "passive"))
      (node (ref "C8") (pin "2") (pinfunction "2_2") (pintype "passive"))
      (node (ref "C9") (pin "2") (pinfunction "2_2") (pintype "passive"))
      (node (ref "IC4") (pin "8") (pinfunction "VCC_8") (pintype "power_in"))
      (node (ref "IC5") (pin "8") (pinfunction "VCC_8") (pintype "power_in"))
      (node (ref "IC6") (pin "8") (pinfunction "VCC_8") (pintype "power_in"))
      (node (ref "IC7") (pin "1") (pinfunction "VCC_1") (pintype "power_in"))
    )
    (net (code "67") (name "P3V3_MP") (class "Default")
      (node (ref "C11") (pin "2") (pinfunction "2_2") (pintype "passive"))
      (node (ref "C12") (pin "2") (pinfunction "2_2") (pintype "passive"))
      (node (ref "C13") (pin "2") (pinfunction "2_2") (pintype "passive"))
      (node (ref "D4") (pin "5") (pinfunction "VBUS_5") (pintype "power_in"))
      (node (ref "IC10") (pin "8") (pinfunction "VCC_8") (pintype "power_in"))
      (node (ref "IC8") (pin "4") (pinfunction "VCC_4") (pintype "power_in"))
      (node (ref "IC9") (pin "8") (pinfunction "+VS_8") (pintype "power_in"))
      (node (ref "J2") (pin "30") (pinfunction "30_30") (pintype "bidirectional"))
      (node (ref "R51") (pin "2") (pinfunction "2_2") (pintype "passive"))
      (node (ref "R52") (pin "2") (pinfunction "2_2") (pintype "passive"))
      (node (ref "R53") (pin "1") (pinfunction "1_1") (pintype "passive"))
      (node (ref "R54") (pin "1") (pinfunction "1_1") (pintype "passive"))
      (node (ref "R55") (pin "2") (pinfunction "2_2") (pintype "passive"))
      (node (ref "R56") (pin "2") (pinfunction "2_2") (pintype "passive"))
      (node (ref "TP3") (pin "1") (pinfunction "1_1") (pintype "bidirectional"))
    )
    (net (code "68") (name "P12V0") (class "Default")
      (node (ref "J2") (pin "28") (pinfunction "28_28") (pintype "bidirectional"))
      (node (ref "J2") (pin "29") (pinfunction "29_29") (pintype "bidirectional"))
      (node (ref "R48") (pin "1") (pinfunction "1_1") (pintype "passive"))
    )
    (net (code "69") (name "P12V0_CPCIS") (class "Default")
      (node (ref "R48") (pin "2") (pinfunction "2_2") (pintype "passive"))
    )
    (net (code "70") (name "unconnected-(D4-I{slash}O1-Pad1)") (class "Default")
      (node (ref "D4") (pin "1") (pinfunction "I/O1_1") (pintype "bidirectional+no_connect"))
    )
    (net (code "71") (name "unconnected-(D4-I{slash}O4-Pad6)") (class "Default")
      (node (ref "D4") (pin "6") (pinfunction "I/O4_6") (pintype "bidirectional+no_connect"))
    )
    (net (code "72") (name "unconnected-(IC8-NC-Pad5)") (class "Default")
      (node (ref "IC8") (pin "5") (pinfunction "NC_5") (pintype "passive+no_connect"))
    )
    (net (code "73") (name "unconnected-(IC10-NC-Pad7)") (class "Default")
      (node (ref "IC10") (pin "7") (pinfunction "NC_7") (pintype "passive+no_connect"))
    )
  )
)
